# connectors.net
KiCad netlist of a schematic drawn in Altium Designer
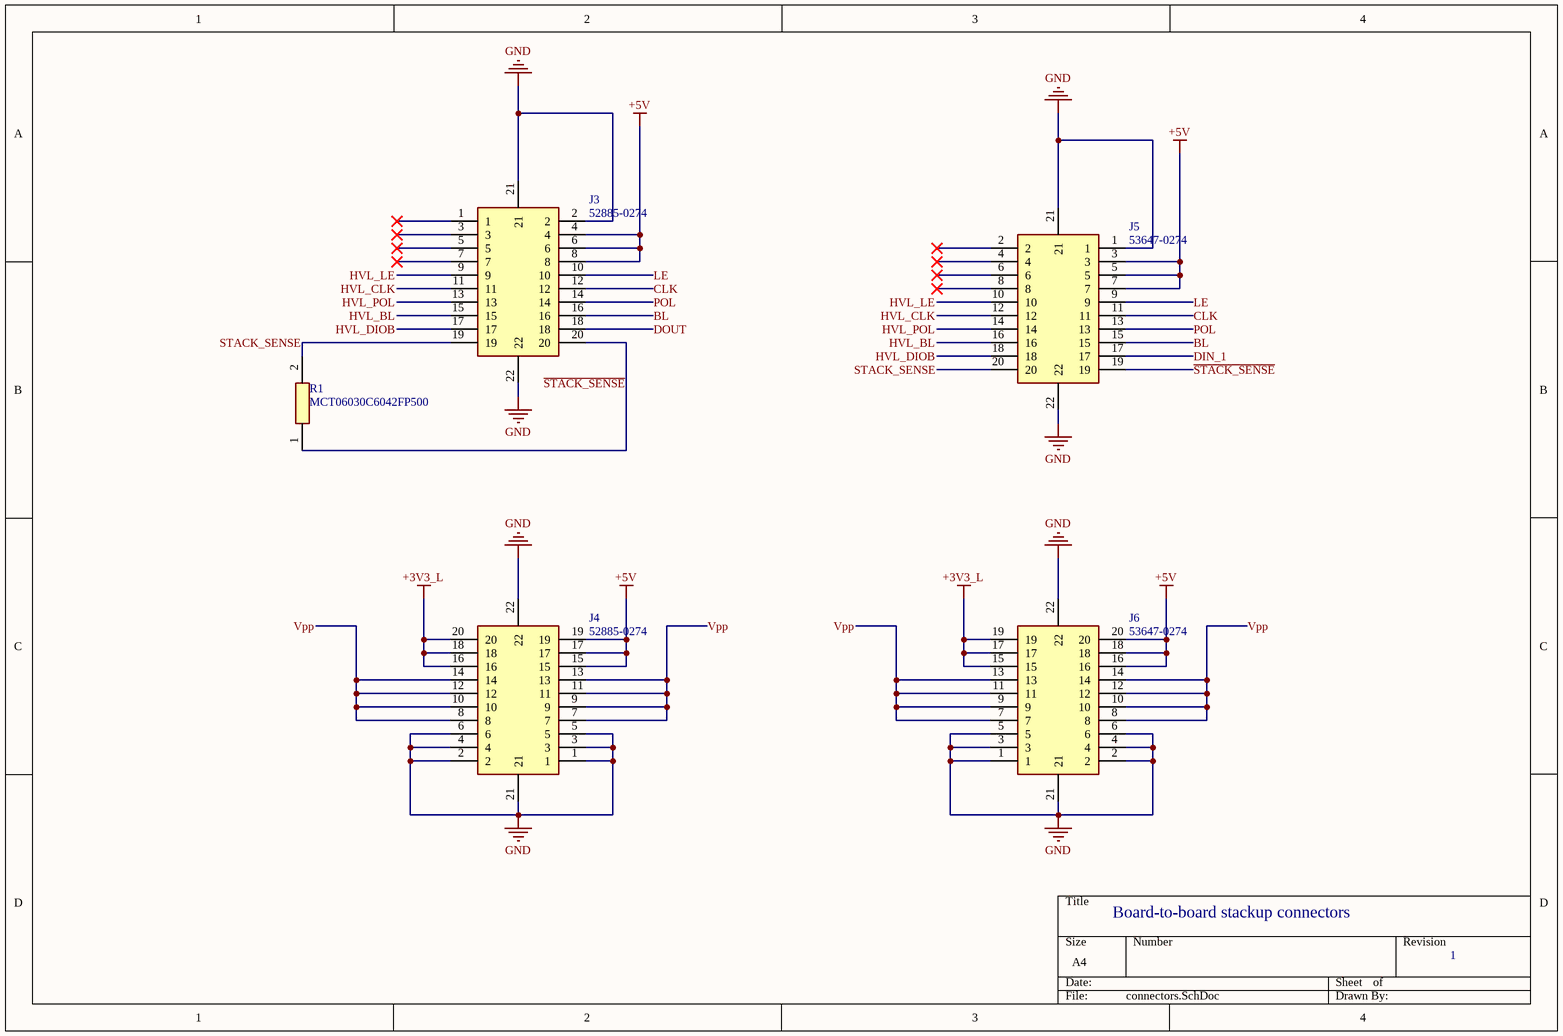
[diagram p0: connectors.SchDoc]

(export (version "E")
  (design (tool "Eeschema 10.0.6"))
  (components
    (comp (ref "J3")
      (value "52885-0274")
      (footprint "528850274")
      (description "Connector")
      (fields (field (name "MOUSER PART NUMBER") "538-52885-0274"))
      (libsource (lib "") (part "52885-0274_1"))
    )
    (comp (ref "J4")
      (value "52885-0274")
      (footprint "528850274")
      (description "Connector")
      (fields (field (name "MOUSER PART NUMBER") "538-52885-0274"))
      (libsource (lib "Switching_Circuit_Components") (part "52885-0274"))
    )
    (comp (ref "J5")
      (value "53647-0274")
      (footprint "536470274")
      (description "Connector")
      (fields (field (name "MOUSER PART NUMBER") "538-53647-0274"))
      (libsource (lib "Switching_Circuit_Components") (part "53647-0274"))
    )
    (comp (ref "J6")
      (value "53647-0274")
      (footprint "536470274")
      (description "Connector")
      (fields (field (name "MOUSER PART NUMBER") "538-53647-0274"))
      (libsource (lib "") (part "53647-0274_1"))
    )
    (comp (ref "R1")
      (value "MCT06030C6042FP500")
      (footprint "SamacSys:RESC1608X55N")
      (description "Resistor")
      (libsource (lib "*") (part "MCT06030C6042FP500"))
    )
  )
  (nets
    (net (code "1") (name "+3V3_L") (class "Default")
      (node (ref "J4") (pin "16") (pinfunction "16_16") (pintype "passive"))
      (node (ref "J4") (pin "18") (pinfunction "18_18") (pintype "passive"))
      (node (ref "J4") (pin "20") (pinfunction "20_20") (pintype "passive"))
      (node (ref "J6") (pin "15") (pinfunction "15_15") (pintype "passive"))
      (node (ref "J6") (pin "17") (pinfunction "17_17") (pintype "passive"))
      (node (ref "J6") (pin "19") (pinfunction "19_19") (pintype "passive"))
    )
    (net (code "2") (name "+5V") (class "Default")
      (node (ref "J3") (pin "4") (pinfunction "4_4") (pintype "passive"))
      (node (ref "J3") (pin "6") (pinfunction "6_6") (pintype "passive"))
      (node (ref "J3") (pin "8") (pinfunction "8_8") (pintype "passive"))
      (node (ref "J4") (pin "15") (pinfunction "15_15") (pintype "passive"))
      (node (ref "J4") (pin "17") (pinfunction "17_17") (pintype "passive"))
      (node (ref "J4") (pin "19") (pinfunction "19_19") (pintype "passive"))
      (node (ref "J5") (pin "3") (pinfunction "3_3") (pintype "passive"))
      (node (ref "J5") (pin "5") (pinfunction "5_5") (pintype "passive"))
      (node (ref "J5") (pin "7") (pinfunction "7_7") (pintype "passive"))
      (node (ref "J6") (pin "16") (pinfunction "16_16") (pintype "passive"))
      (node (ref "J6") (pin "18") (pinfunction "18_18") (pintype "passive"))
      (node (ref "J6") (pin "20") (pinfunction "20_20") (pintype "passive"))
    )
    (net (code "3") (name "/BL") (class "Default")
      (node (ref "J3") (pin "16") (pinfunction "16_16") (pintype "passive"))
      (node (ref "J5") (pin "15") (pinfunction "15_15") (pintype "passive"))
    )
    (net (code "4") (name "/CLK") (class "Default")
      (node (ref "J3") (pin "12") (pinfunction "12_12") (pintype "passive"))
      (node (ref "J5") (pin "11") (pinfunction "11_11") (pintype "passive"))
    )
    (net (code "5") (name "/DIN_1") (class "Default")
      (node (ref "J5") (pin "17") (pinfunction "17_17") (pintype "passive"))
    )
    (net (code "6") (name "/DOUT") (class "Default")
      (node (ref "J3") (pin "18") (pinfunction "18_18") (pintype "passive"))
    )
    (net (code "7") (name "/HVL_BL") (class "Default")
      (node (ref "J3") (pin "15") (pinfunction "15_15") (pintype "passive"))
      (node (ref "J5") (pin "16") (pinfunction "16_16") (pintype "passive"))
    )
    (net (code "8") (name "/HVL_CLK") (class "Default")
      (node (ref "J3") (pin "11") (pinfunction "11_11") (pintype "passive"))
      (node (ref "J5") (pin "12") (pinfunction "12_12") (pintype "passive"))
    )
    (net (code "9") (name "/HVL_DIOB") (class "Default")
      (node (ref "J3") (pin "17") (pinfunction "17_17") (pintype "passive"))
      (node (ref "J5") (pin "18") (pinfunction "18_18") (pintype "passive"))
    )
    (net (code "10") (name "/HVL_LE") (class "Default")
      (node (ref "J3") (pin "9") (pinfunction "9_9") (pintype "passive"))
      (node (ref "J5") (pin "10") (pinfunction "10_10") (pintype "passive"))
    )
    (net (code "11") (name "/HVL_POL") (class "Default")
      (node (ref "J3") (pin "13") (pinfunction "13_13") (pintype "passive"))
      (node (ref "J5") (pin "14") (pinfunction "14_14") (pintype "passive"))
    )
    (net (code "12") (name "/LE") (class "Default")
      (node (ref "J3") (pin "10") (pinfunction "10_10") (pintype "passive"))
      (node (ref "J5") (pin "9") (pinfunction "9_9") (pintype "passive"))
    )
    (net (code "13") (name "/POL") (class "Default")
      (node (ref "J3") (pin "14") (pinfunction "14_14") (pintype "passive"))
      (node (ref "J5") (pin "13") (pinfunction "13_13") (pintype "passive"))
    )
    (net (code "14") (name "/STACK_SENSE") (class "Default")
      (node (ref "J3") (pin "19") (pinfunction "19_19") (pintype "passive"))
      (node (ref "J5") (pin "20") (pinfunction "20_20") (pintype "passive"))
      (node (ref "R1") (pin "2") (pinfunction "2_2") (pintype "passive"))
    )
    (net (code "15") (name "/Vpp") (class "Default")
      (node (ref "J4") (pin "10") (pinfunction "10_10") (pintype "passive"))
      (node (ref "J4") (pin "11") (pinfunction "11_11") (pintype "passive"))
      (node (ref "J4") (pin "12") (pinfunction "12_12") (pintype "passive"))
      (node (ref "J4") (pin "13") (pinfunction "13_13") (pintype "passive"))
      (node (ref "J4") (pin "14") (pinfunction "14_14") (pintype "passive"))
      (node (ref "J4") (pin "7") (pinfunction "7_7") (pintype "passive"))
      (node (ref "J4") (pin "8") (pinfunction "8_8") (pintype "passive"))
      (node (ref "J4") (pin "9") (pinfunction "9_9") (pintype "passive"))
      (node (ref "J6") (pin "10") (pinfunction "10_10") (pintype "passive"))
      (node (ref "J6") (pin "11") (pinfunction "11_11") (pintype "passive"))
      (node (ref "J6") (pin "12") (pinfunction "12_12") (pintype "passive"))
      (node (ref "J6") (pin "13") (pinfunction "13_13") (pintype "passive"))
      (node (ref "J6") (pin "14") (pinfunction "14_14") (pintype "passive"))
      (node (ref "J6") (pin "7") (pinfunction "7_7") (pintype "passive"))
      (node (ref "J6") (pin "8") (pinfunction "8_8") (pintype "passive"))
      (node (ref "J6") (pin "9") (pinfunction "9_9") (pintype "passive"))
    )
    (net (code "16") (name "/~{STACK_SENSE}") (class "Default")
      (node (ref "J3") (pin "20") (pinfunction "20_20") (pintype "passive"))
      (node (ref "J5") (pin "19") (pinfunction "19_19") (pintype "passive"))
      (node (ref "R1") (pin "1") (pinfunction "1_1") (pintype "passive"))
    )
    (net (code "17") (name "GND") (class "Default")
      (node (ref "J3") (pin "2") (pinfunction "2_2") (pintype "passive"))
      (node (ref "J3") (pin "21") (pinfunction "21_21") (pintype "passive"))
      (node (ref "J3") (pin "22") (pinfunction "22_22") (pintype "passive"))
      (node (ref "J4") (pin "1") (pinfunction "1_1") (pintype "passive"))
      (node (ref "J4") (pin "2") (pinfunction "2_2") (pintype "passive"))
      (node (ref "J4") (pin "21") (pinfunction "21_21") (pintype "passive"))
      (node (ref "J4") (pin "22") (pinfunction "22_22") (pintype "passive"))
      (node (ref "J4") (pin "3") (pinfunction "3_3") (pintype "passive"))
      (node (ref "J4") (pin "4") (pinfunction "4_4") (pintype "passive"))
      (node (ref "J4") (pin "5") (pinfunction "5_5") (pintype "passive"))
      (node (ref "J4") (pin "6") (pinfunction "6_6") (pintype "passive"))
      (node (ref "J5") (pin "1") (pinfunction "1_1") (pintype "passive"))
      (node (ref "J5") (pin "21") (pinfunction "21_21") (pintype "passive"))
      (node (ref "J5") (pin "22") (pinfunction "22_22") (pintype "passive"))
      (node (ref "J6") (pin "1") (pinfunction "1_1") (pintype "passive"))
      (node (ref "J6") (pin "2") (pinfunction "2_2") (pintype "passive"))
      (node (ref "J6") (pin "21") (pinfunction "21_21") (pintype "passive"))
      (node (ref "J6") (pin "22") (pinfunction "22_22") (pintype "passive"))
      (node (ref "J6") (pin "3") (pinfunction "3_3") (pintype "passive"))
      (node (ref "J6") (pin "4") (pinfunction "4_4") (pintype "passive"))
      (node (ref "J6") (pin "5") (pinfunction "5_5") (pintype "passive"))
      (node (ref "J6") (pin "6") (pinfunction "6_6") (pintype "passive"))
    )
    (net (code "18") (name "unconnected-(J3-Pad1)") (class "Default")
      (node (ref "J3") (pin "1") (pinfunction "1_1") (pintype "passive+no_connect"))
    )
    (net (code "19") (name "unconnected-(J3-Pad3)") (class "Default")
      (node (ref "J3") (pin "3") (pinfunction "3_3") (pintype "passive+no_connect"))
    )
    (net (code "20") (name "unconnected-(J3-Pad5)") (class "Default")
      (node (ref "J3") (pin "5") (pinfunction "5_5") (pintype "passive+no_connect"))
    )
    (net (code "21") (name "unconnected-(J3-Pad7)") (class "Default")
      (node (ref "J3") (pin "7") (pinfunction "7_7") (pintype "passive+no_connect"))
    )
    (net (code "22") (name "unconnected-(J5-Pad2)") (class "Default")
      (node (ref "J5") (pin "2") (pinfunction "2_2") (pintype "passive+no_connect"))
    )
    (net (code "23") (name "unconnected-(J5-Pad4)") (class "Default")
      (node (ref "J5") (pin "4") (pinfunction "4_4") (pintype "passive+no_connect"))
    )
    (net (code "24") (name "unconnected-(J5-Pad6)") (class "Default")
      (node (ref "J5") (pin "6") (pinfunction "6_6") (pintype "passive+no_connect"))
    )
    (net (code "25") (name "unconnected-(J5-Pad8)") (class "Default")
      (node (ref "J5") (pin "8") (pinfunction "8_8") (pintype "passive+no_connect"))
    )
  )
)
